# WT8266_universal_v01.net
KiCad netlist of a schematic drawn in EAGLE
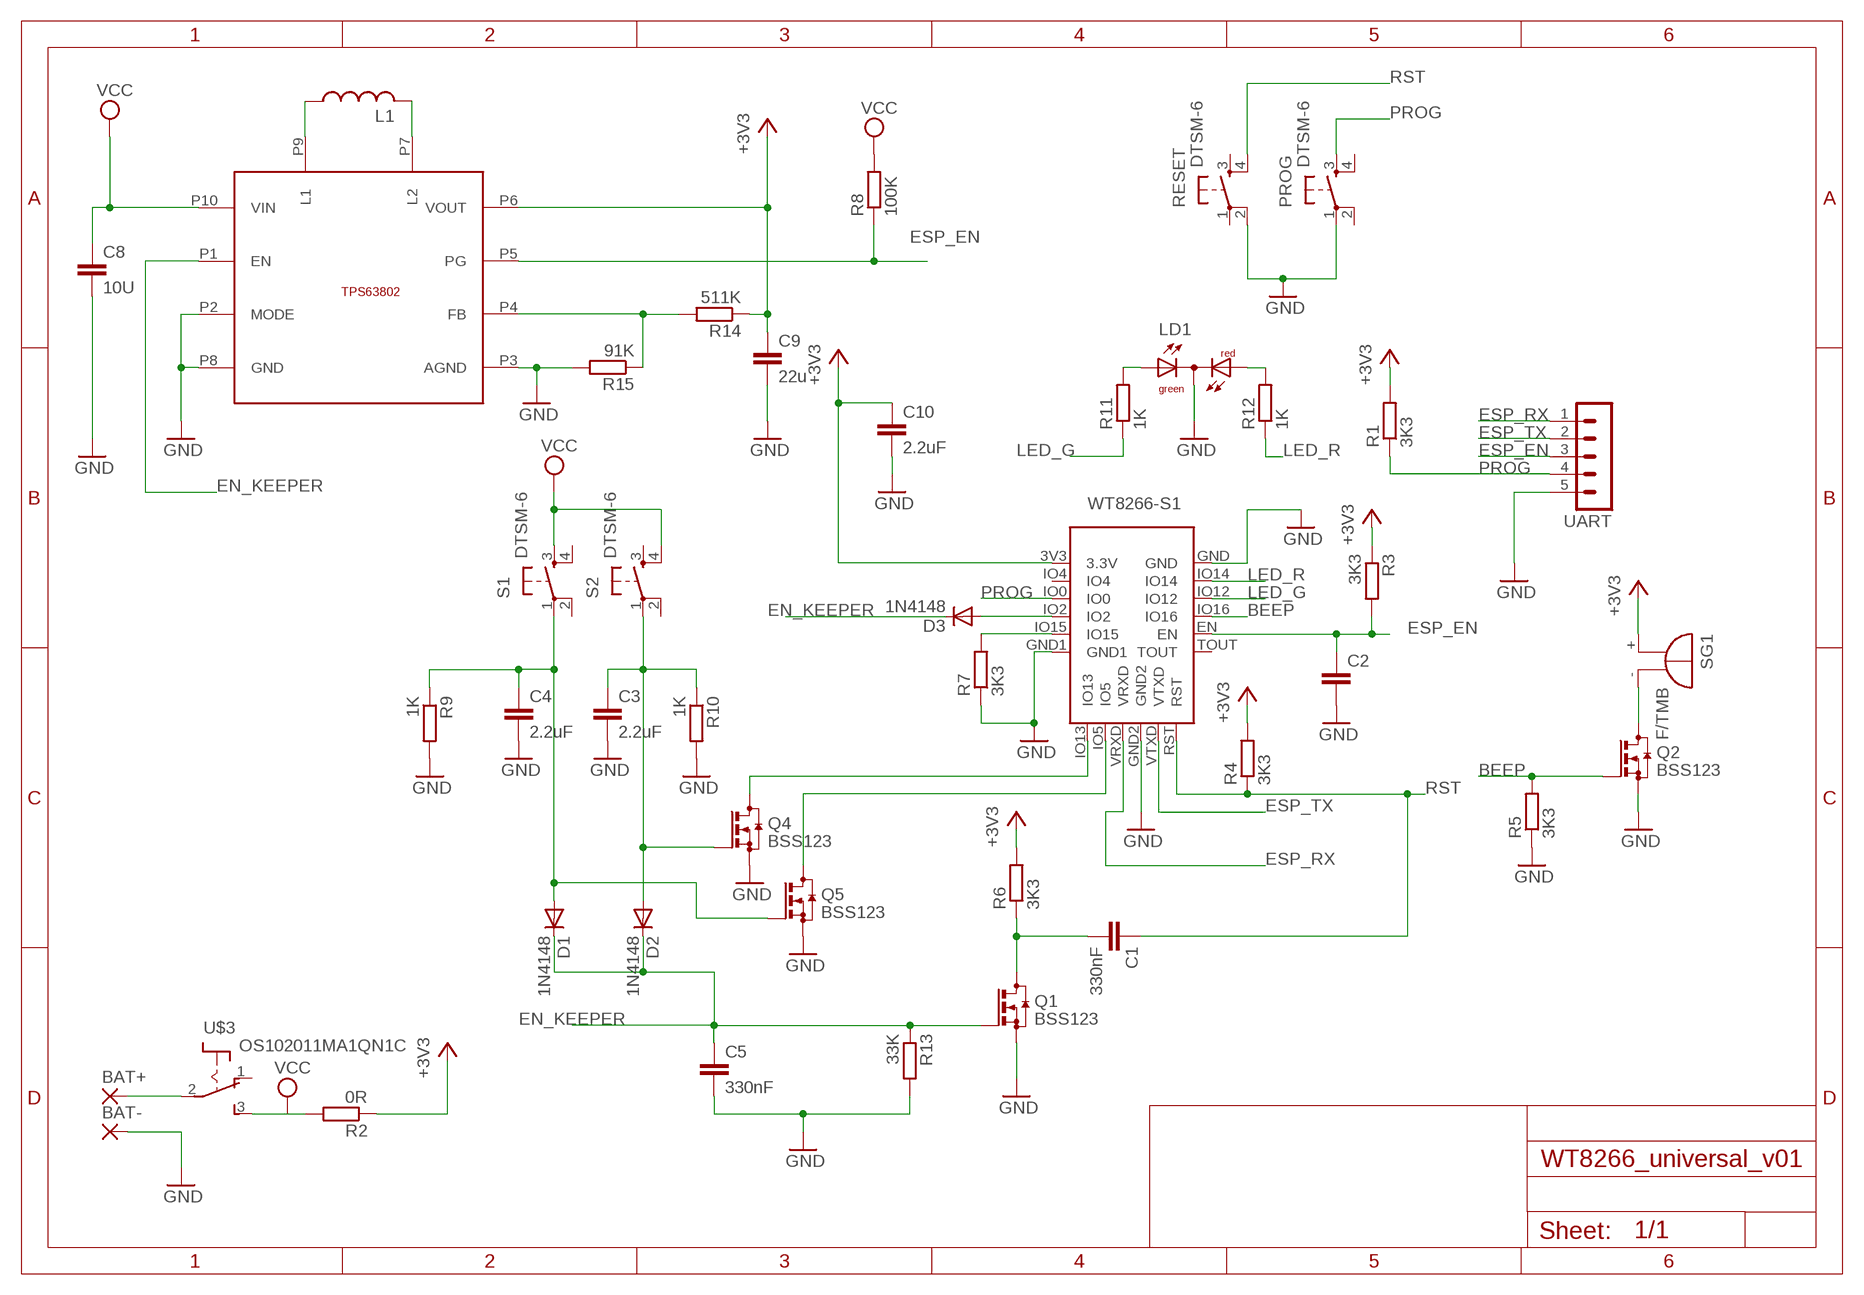
[diagram p0: schematic, sheet 1]

(export (version "E")
  (design (tool "Eeschema 10.0.6"))
  (components
    (comp (ref "BAT+")
      (value "2,54/1,0")
      (footprint "eagle-import:2,54_1,0")
      (libsource (lib "eagle-import") (part "2,54/1,0"))
    )
    (comp (ref "BAT-")
      (value "2,54/1,0")
      (footprint "eagle-import:2,54_1,0")
      (libsource (lib "eagle-import") (part "2,54/1,0"))
    )
    (comp (ref "C1")
      (value "330nF")
      (footprint "eagle-import:C0805")
      (libsource (lib "eagle-import") (part "C-EUC0805"))
    )
    (comp (ref "C2")
      (value "C-EUC0805")
      (footprint "eagle-import:C0805")
      (libsource (lib "eagle-import") (part "C-EUC0805"))
    )
    (comp (ref "C3")
      (value "2.2uF")
      (footprint "eagle-import:C0805")
      (libsource (lib "eagle-import") (part "C-EUC0805"))
    )
    (comp (ref "C4")
      (value "2.2uF")
      (footprint "eagle-import:C0805")
      (libsource (lib "eagle-import") (part "C-EUC0805"))
    )
    (comp (ref "C5")
      (value "330nF")
      (footprint "eagle-import:C0805")
      (libsource (lib "eagle-import") (part "C-EUC0805"))
    )
    (comp (ref "C8")
      (value "10U")
      (footprint "eagle-import:C0805")
      (libsource (lib "eagle-import") (part "C-EUC0805"))
    )
    (comp (ref "C9")
      (value "22u")
      (footprint "eagle-import:C0805")
      (libsource (lib "eagle-import") (part "C-EUC0805"))
    )
    (comp (ref "C10")
      (value "2.2uF")
      (footprint "eagle-import:C0805")
      (libsource (lib "eagle-import") (part "C-EUC0805"))
    )
    (comp (ref "D1")
      (value "1N4148")
      (footprint "eagle-import:0805")
      (libsource (lib "eagle-import") (part "1N4148"))
    )
    (comp (ref "D2")
      (value "1N4148")
      (footprint "eagle-import:0805")
      (libsource (lib "eagle-import") (part "1N4148"))
    )
    (comp (ref "D3")
      (value "1N4148")
      (footprint "eagle-import:0805")
      (libsource (lib "eagle-import") (part "1N4148"))
    )
    (comp (ref "L1")
      (value "L-USL2825P")
      (footprint "eagle-import:L2825P")
      (libsource (lib "eagle-import") (part "L-USL2825P"))
    )
    (comp (ref "LD1")
      (value "DUOLED-RG-C3MM")
      (footprint "eagle-import:DUOLED-A-3MM")
      (libsource (lib "eagle-import") (part "DUOLED-RG-C3MM"))
    )
    (comp (ref "PROG")
      (value "DTSM-6")
      (footprint "eagle-import:DTSM-6")
      (libsource (lib "eagle-import") (part "DTSM-6"))
    )
    (comp (ref "Q1")
      (value "BSS123")
      (footprint "eagle-import:SOT23")
      (libsource (lib "eagle-import") (part "BSS123"))
    )
    (comp (ref "Q2")
      (value "BSS123")
      (footprint "eagle-import:SOT23")
      (libsource (lib "eagle-import") (part "BSS123"))
    )
    (comp (ref "Q4")
      (value "BSS123")
      (footprint "eagle-import:SOT23")
      (libsource (lib "eagle-import") (part "BSS123"))
    )
    (comp (ref "Q5")
      (value "BSS123")
      (footprint "eagle-import:SOT23")
      (libsource (lib "eagle-import") (part "BSS123"))
    )
    (comp (ref "R1")
      (value "3K3")
      (footprint "eagle-import:R0805")
      (libsource (lib "eagle-import") (part "R-EU_R0805"))
    )
    (comp (ref "R2")
      (value "0R")
      (footprint "eagle-import:R0805")
      (libsource (lib "eagle-import") (part "R-EU_R0805"))
    )
    (comp (ref "R3")
      (value "3K3")
      (footprint "eagle-import:R0805")
      (libsource (lib "eagle-import") (part "R-EU_R0805"))
    )
    (comp (ref "R4")
      (value "3K3")
      (footprint "eagle-import:R0805")
      (libsource (lib "eagle-import") (part "R-EU_R0805"))
    )
    (comp (ref "R5")
      (value "3K3")
      (footprint "eagle-import:R0805")
      (libsource (lib "eagle-import") (part "R-EU_R0805"))
    )
    (comp (ref "R6")
      (value "3K3")
      (footprint "eagle-import:R0805")
      (libsource (lib "eagle-import") (part "R-EU_R0805"))
    )
    (comp (ref "R7")
      (value "3K3")
      (footprint "eagle-import:R0805")
      (libsource (lib "eagle-import") (part "R-EU_R0805"))
    )
    (comp (ref "R8")
      (value "100K")
      (footprint "eagle-import:R0805")
      (libsource (lib "eagle-import") (part "R-EU_R0805"))
    )
    (comp (ref "R9")
      (value "1K")
      (footprint "eagle-import:R0805")
      (libsource (lib "eagle-import") (part "R-EU_R0805"))
    )
    (comp (ref "R10")
      (value "1K")
      (footprint "eagle-import:R0805")
      (libsource (lib "eagle-import") (part "R-EU_R0805"))
    )
    (comp (ref "R11")
      (value "1K")
      (footprint "eagle-import:R0805")
      (libsource (lib "eagle-import") (part "R-EU_R0805"))
    )
    (comp (ref "R12")
      (value "1K")
      (footprint "eagle-import:R0805")
      (libsource (lib "eagle-import") (part "R-EU_R0805"))
    )
    (comp (ref "R13")
      (value "33K")
      (footprint "eagle-import:R0805")
      (libsource (lib "eagle-import") (part "R-EU_R0805"))
    )
    (comp (ref "R14")
      (value "511K")
      (footprint "eagle-import:R0805")
      (libsource (lib "eagle-import") (part "R-EU_R0805"))
    )
    (comp (ref "R15")
      (value "91K")
      (footprint "eagle-import:R0805")
      (libsource (lib "eagle-import") (part "R-EU_R0805"))
    )
    (comp (ref "RESET")
      (value "DTSM-6")
      (footprint "eagle-import:DTSM-6")
      (libsource (lib "eagle-import") (part "DTSM-6"))
    )
    (comp (ref "S1")
      (value "DTSM-6")
      (footprint "eagle-import:DTSM-6")
      (libsource (lib "eagle-import") (part "DTSM-6"))
    )
    (comp (ref "S2")
      (value "DTSM-6")
      (footprint "eagle-import:DTSM-6")
      (libsource (lib "eagle-import") (part "DTSM-6"))
    )
    (comp (ref "SG1")
      (value "F/TMB")
      (footprint "eagle-import:F_TMB")
      (libsource (lib "eagle-import") (part "F/TMB"))
    )
    (comp (ref "U$1")
      (value "WT8266-S1")
      (footprint "eagle-import:WT8266-S1")
      (libsource (lib "eagle-import") (part "WT8266-S1"))
    )
    (comp (ref "U$3")
      (value "OS102011MA1QN1C")
      (footprint "eagle-import:OS102011MA1QN1C")
      (libsource (lib "eagle-import") (part "OS102011MA1QN1C"))
    )
    (comp (ref "U$4")
      (value "TPS63802")
      (footprint "eagle-import:VSON-HR-10")
      (libsource (lib "eagle-import") (part "TPS63802"))
    )
    (comp (ref "UART")
      (value "MAR05-1")
      (footprint "eagle-import:MAR05-1")
      (libsource (lib "eagle-import") (part "MAR05-1"))
    )
  )
  (nets
    (net (code "1") (name "+3V3") (class "Default")
      (node (ref "C10") (pin "1") (pinfunction "1_1") (pintype "passive"))
      (node (ref "C9") (pin "1") (pinfunction "1_1") (pintype "passive"))
      (node (ref "R1") (pin "2") (pinfunction "2_2") (pintype "passive"))
      (node (ref "R14") (pin "1") (pinfunction "1_1") (pintype "passive"))
      (node (ref "R2") (pin "1") (pinfunction "1_1") (pintype "passive"))
      (node (ref "R3") (pin "1") (pinfunction "1_1") (pintype "passive"))
      (node (ref "R4") (pin "2") (pinfunction "2_2") (pintype "passive"))
      (node (ref "R6") (pin "2") (pinfunction "2_2") (pintype "passive"))
      (node (ref "SG1") (pin "+") (pinfunction "+_+") (pintype "passive"))
      (node (ref "U$1") (pin "3V3") (pinfunction "3.3V_3V3") (pintype "bidirectional"))
      (node (ref "U$4") (pin "P6") (pinfunction "VOUT_P6") (pintype "bidirectional"))
    )
    (net (code "2") (name "/BEEP") (class "Default")
      (node (ref "Q2") (pin "1") (pinfunction "G_1") (pintype "passive"))
      (node (ref "R5") (pin "2") (pinfunction "2_2") (pintype "passive"))
      (node (ref "U$1") (pin "IO16") (pinfunction "IO16_IO16") (pintype "bidirectional"))
    )
    (net (code "3") (name "/EN_KEEPER") (class "Default")
      (node (ref "C5") (pin "1") (pinfunction "1_1") (pintype "passive"))
      (node (ref "D1") (pin "1") (pinfunction "C_1") (pintype "passive"))
      (node (ref "D2") (pin "1") (pinfunction "C_1") (pintype "passive"))
      (node (ref "D3") (pin "1") (pinfunction "C_1") (pintype "passive"))
      (node (ref "Q1") (pin "1") (pinfunction "G_1") (pintype "passive"))
      (node (ref "R13") (pin "1") (pinfunction "1_1") (pintype "passive"))
      (node (ref "U$4") (pin "P1") (pinfunction "EN_P1") (pintype "bidirectional"))
    )
    (net (code "4") (name "/ESP_EN") (class "Default")
      (node (ref "C2") (pin "1") (pinfunction "1_1") (pintype "passive"))
      (node (ref "R3") (pin "2") (pinfunction "2_2") (pintype "passive"))
      (node (ref "R8") (pin "1") (pinfunction "1_1") (pintype "passive"))
      (node (ref "U$1") (pin "EN") (pinfunction "EN_EN") (pintype "bidirectional"))
      (node (ref "U$4") (pin "P5") (pinfunction "PG_P5") (pintype "bidirectional"))
      (node (ref "UART") (pin "3") (pinfunction "3_3") (pintype "passive"))
    )
    (net (code "5") (name "/ESP_RX") (class "Default")
      (node (ref "U$1") (pin "VRXD") (pinfunction "VRXD_VRXD") (pintype "bidirectional"))
      (node (ref "UART") (pin "1") (pinfunction "1_1") (pintype "passive"))
    )
    (net (code "6") (name "/ESP_TX") (class "Default")
      (node (ref "U$1") (pin "VTXD") (pinfunction "VTXD_VTXD") (pintype "bidirectional"))
      (node (ref "UART") (pin "2") (pinfunction "2_2") (pintype "passive"))
    )
    (net (code "7") (name "/LED_G") (class "Default")
      (node (ref "R11") (pin "1") (pinfunction "1_1") (pintype "passive"))
      (node (ref "U$1") (pin "IO12") (pinfunction "IO12_IO12") (pintype "bidirectional"))
    )
    (net (code "8") (name "/LED_R") (class "Default")
      (node (ref "R12") (pin "1") (pinfunction "1_1") (pintype "passive"))
      (node (ref "U$1") (pin "IO14") (pinfunction "IO14_IO14") (pintype "bidirectional"))
    )
    (net (code "9") (name "/PROG") (class "Default")
      (node (ref "PROG") (pin "3") (pinfunction "3_3") (pintype "passive"))
      (node (ref "R1") (pin "1") (pinfunction "1_1") (pintype "passive"))
      (node (ref "U$1") (pin "IO0") (pinfunction "IO0_IO0") (pintype "bidirectional"))
      (node (ref "UART") (pin "4") (pinfunction "4_4") (pintype "passive"))
    )
    (net (code "10") (name "/RST") (class "Default")
      (node (ref "C1") (pin "1") (pinfunction "1_1") (pintype "passive"))
      (node (ref "R4") (pin "1") (pinfunction "1_1") (pintype "passive"))
      (node (ref "RESET") (pin "4") (pinfunction "4_4") (pintype "passive"))
      (node (ref "U$1") (pin "RST") (pinfunction "RST_RST") (pintype "bidirectional"))
    )
    (net (code "11") (name "GND") (class "Default")
      (node (ref "BAT-") (pin "1") (pinfunction "P_1") (pintype "passive"))
      (node (ref "C10") (pin "2") (pinfunction "2_2") (pintype "passive"))
      (node (ref "C2") (pin "2") (pinfunction "2_2") (pintype "passive"))
      (node (ref "C3") (pin "2") (pinfunction "2_2") (pintype "passive"))
      (node (ref "C4") (pin "2") (pinfunction "2_2") (pintype "passive"))
      (node (ref "C5") (pin "2") (pinfunction "2_2") (pintype "passive"))
      (node (ref "C8") (pin "2") (pinfunction "2_2") (pintype "passive"))
      (node (ref "C9") (pin "2") (pinfunction "2_2") (pintype "passive"))
      (node (ref "LD1") (pin "2") (pinfunction "C_2") (pintype "passive"))
      (node (ref "PROG") (pin "1") (pinfunction "1_1") (pintype "passive"))
      (node (ref "Q1") (pin "2") (pinfunction "S_2") (pintype "passive"))
      (node (ref "Q2") (pin "2") (pinfunction "S_2") (pintype "passive"))
      (node (ref "Q4") (pin "2") (pinfunction "S_2") (pintype "passive"))
      (node (ref "Q5") (pin "2") (pinfunction "S_2") (pintype "passive"))
      (node (ref "R10") (pin "2") (pinfunction "2_2") (pintype "passive"))
      (node (ref "R13") (pin "2") (pinfunction "2_2") (pintype "passive"))
      (node (ref "R15") (pin "2") (pinfunction "2_2") (pintype "passive"))
      (node (ref "R5") (pin "1") (pinfunction "1_1") (pintype "passive"))
      (node (ref "R7") (pin "1") (pinfunction "1_1") (pintype "passive"))
      (node (ref "R9") (pin "2") (pinfunction "2_2") (pintype "passive"))
      (node (ref "RESET") (pin "2") (pinfunction "2_2") (pintype "passive"))
      (node (ref "U$1") (pin "GND") (pinfunction "GND_GND") (pintype "bidirectional"))
      (node (ref "U$1") (pin "GND1") (pinfunction "GND1_GND1") (pintype "bidirectional"))
      (node (ref "U$1") (pin "GND2") (pinfunction "GND2_GND2") (pintype "bidirectional"))
      (node (ref "U$4") (pin "P2") (pinfunction "MODE_P2") (pintype "bidirectional"))
      (node (ref "U$4") (pin "P3") (pinfunction "AGND_P3") (pintype "bidirectional"))
      (node (ref "U$4") (pin "P8") (pinfunction "GND_P8") (pintype "bidirectional"))
      (node (ref "UART") (pin "5") (pinfunction "5_5") (pintype "passive"))
    )
    (net (code "12") (name "Net-(BAT+-P)") (class "Default")
      (node (ref "BAT+") (pin "1") (pinfunction "P_1") (pintype "passive"))
      (node (ref "U$3") (pin "2") (pinfunction "P_2") (pintype "passive"))
    )
    (net (code "13") (name "Net-(D1-A)") (class "Default")
      (node (ref "C4") (pin "1") (pinfunction "1_1") (pintype "passive"))
      (node (ref "D1") (pin "2") (pinfunction "A_2") (pintype "passive"))
      (node (ref "Q5") (pin "1") (pinfunction "G_1") (pintype "passive"))
      (node (ref "R9") (pin "1") (pinfunction "1_1") (pintype "passive"))
      (node (ref "S1") (pin "1") (pinfunction "1_1") (pintype "passive"))
    )
    (net (code "14") (name "Net-(D2-A)") (class "Default")
      (node (ref "C3") (pin "1") (pinfunction "1_1") (pintype "passive"))
      (node (ref "D2") (pin "2") (pinfunction "A_2") (pintype "passive"))
      (node (ref "Q4") (pin "1") (pinfunction "G_1") (pintype "passive"))
      (node (ref "R10") (pin "1") (pinfunction "1_1") (pintype "passive"))
      (node (ref "S2") (pin "1") (pinfunction "1_1") (pintype "passive"))
    )
    (net (code "15") (name "Net-(D3-A)") (class "Default")
      (node (ref "D3") (pin "2") (pinfunction "A_2") (pintype "passive"))
      (node (ref "U$1") (pin "IO2") (pinfunction "IO2_IO2") (pintype "bidirectional"))
    )
    (net (code "16") (name "Net-(LD1-AG)") (class "Default")
      (node (ref "LD1") (pin "1") (pinfunction "AG_1") (pintype "passive"))
      (node (ref "R11") (pin "2") (pinfunction "2_2") (pintype "passive"))
    )
    (net (code "17") (name "Net-(LD1-AR)") (class "Default")
      (node (ref "LD1") (pin "3") (pinfunction "AR_3") (pintype "passive"))
      (node (ref "R12") (pin "2") (pinfunction "2_2") (pintype "passive"))
    )
    (net (code "18") (name "Net-(Q1-D)") (class "Default")
      (node (ref "C1") (pin "2") (pinfunction "2_2") (pintype "passive"))
      (node (ref "Q1") (pin "3") (pinfunction "D_3") (pintype "passive"))
      (node (ref "R6") (pin "1") (pinfunction "1_1") (pintype "passive"))
    )
    (net (code "19") (name "Net-(Q2-D)") (class "Default")
      (node (ref "Q2") (pin "3") (pinfunction "D_3") (pintype "passive"))
      (node (ref "SG1") (pin "-") (pinfunction "-_-") (pintype "passive"))
    )
    (net (code "20") (name "Net-(Q4-D)") (class "Default")
      (node (ref "Q4") (pin "3") (pinfunction "D_3") (pintype "passive"))
      (node (ref "U$1") (pin "IO13") (pinfunction "IO13_IO13") (pintype "bidirectional"))
    )
    (net (code "21") (name "Net-(Q5-D)") (class "Default")
      (node (ref "Q5") (pin "3") (pinfunction "D_3") (pintype "passive"))
      (node (ref "U$1") (pin "IO5") (pinfunction "IO5_IO5") (pintype "bidirectional"))
    )
    (net (code "22") (name "Net-(R7-Pad2)") (class "Default")
      (node (ref "R7") (pin "2") (pinfunction "2_2") (pintype "passive"))
      (node (ref "U$1") (pin "IO15") (pinfunction "IO15_IO15") (pintype "bidirectional"))
    )
    (net (code "23") (name "Net-(U$4-FB)") (class "Default")
      (node (ref "R14") (pin "2") (pinfunction "2_2") (pintype "passive"))
      (node (ref "R15") (pin "1") (pinfunction "1_1") (pintype "passive"))
      (node (ref "U$4") (pin "P4") (pinfunction "FB_P4") (pintype "bidirectional"))
    )
    (net (code "24") (name "Net-(U$4-L1)") (class "Default")
      (node (ref "L1") (pin "1") (pinfunction "1_1") (pintype "passive"))
      (node (ref "U$4") (pin "P9") (pinfunction "L1_P9") (pintype "bidirectional"))
    )
    (net (code "25") (name "Net-(U$4-L2)") (class "Default")
      (node (ref "L1") (pin "2") (pinfunction "2_2") (pintype "passive"))
      (node (ref "U$4") (pin "P7") (pinfunction "L2_P7") (pintype "bidirectional"))
    )
    (net (code "26") (name "VCC") (class "Default")
      (node (ref "C8") (pin "1") (pinfunction "1_1") (pintype "passive"))
      (node (ref "R2") (pin "2") (pinfunction "2_2") (pintype "passive"))
      (node (ref "R8") (pin "2") (pinfunction "2_2") (pintype "passive"))
      (node (ref "S1") (pin "3") (pinfunction "3_3") (pintype "passive"))
      (node (ref "S2") (pin "4") (pinfunction "4_4") (pintype "passive"))
      (node (ref "U$3") (pin "3") (pinfunction "S_3") (pintype "passive"))
      (node (ref "U$4") (pin "P10") (pinfunction "VIN_P10") (pintype "bidirectional"))
    )
    (net (code "27") (name "unconnected-(PROG-Pad2)") (class "Default")
      (node (ref "PROG") (pin "2") (pinfunction "2_2") (pintype "passive"))
    )
    (net (code "28") (name "unconnected-(PROG-Pad4)") (class "Default")
      (node (ref "PROG") (pin "4") (pinfunction "4_4") (pintype "passive"))
    )
    (net (code "29") (name "unconnected-(RESET-Pad1)") (class "Default")
      (node (ref "RESET") (pin "1") (pinfunction "1_1") (pintype "passive"))
    )
    (net (code "30") (name "unconnected-(RESET-Pad3)") (class "Default")
      (node (ref "RESET") (pin "3") (pinfunction "3_3") (pintype "passive"))
    )
    (net (code "31") (name "unconnected-(S1-Pad2)") (class "Default")
      (node (ref "S1") (pin "2") (pinfunction "2_2") (pintype "passive"))
    )
    (net (code "32") (name "unconnected-(S1-Pad4)") (class "Default")
      (node (ref "S1") (pin "4") (pinfunction "4_4") (pintype "passive"))
    )
    (net (code "33") (name "unconnected-(S2-Pad2)") (class "Default")
      (node (ref "S2") (pin "2") (pinfunction "2_2") (pintype "passive"))
    )
    (net (code "34") (name "unconnected-(S2-Pad3)") (class "Default")
      (node (ref "S2") (pin "3") (pinfunction "3_3") (pintype "passive"))
    )
    (net (code "35") (name "unconnected-(U$1-PadIO4)") (class "Default")
      (node (ref "U$1") (pin "IO4") (pinfunction "IO4_IO4") (pintype "bidirectional"))
    )
    (net (code "36") (name "unconnected-(U$1-PadTOUT)") (class "Default")
      (node (ref "U$1") (pin "TOUT") (pinfunction "TOUT_TOUT") (pintype "bidirectional"))
    )
    (net (code "37") (name "unconnected-(U$3-O-Pad1)") (class "Default")
      (node (ref "U$3") (pin "1") (pinfunction "O_1") (pintype "passive"))
    )
  )
)
